# kolrs868_rx.net
KiCad netlist of a schematic drawn in EAGLE
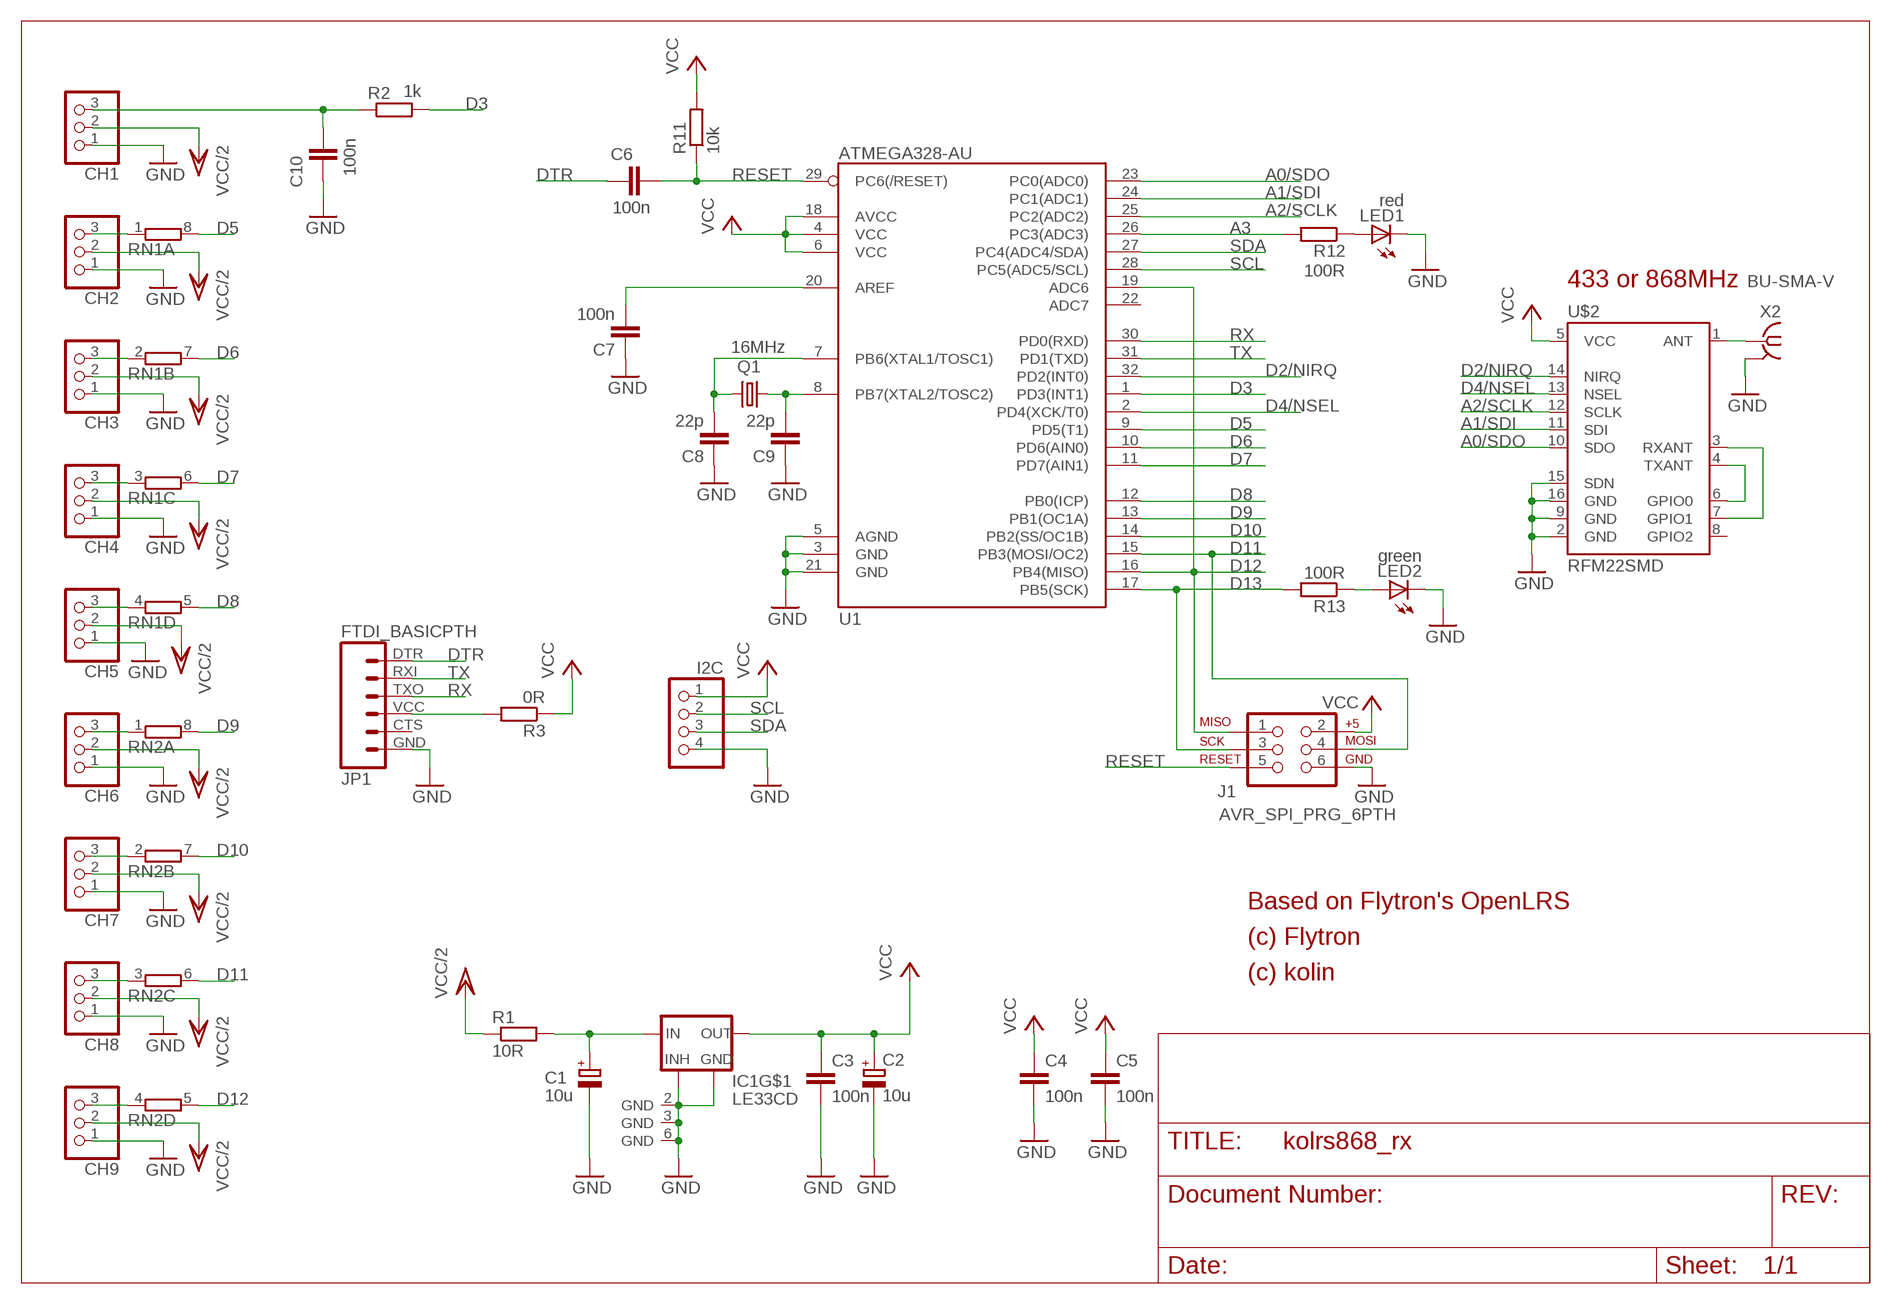
[diagram p0: schematic, sheet 1]

(export (version "E")
  (design (tool "Eeschema 10.0.6"))
  (components
    (comp (ref "C1")
      (value "10u")
      (footprint "eagle-import:SMC_B")
      (libsource (lib "eagle-import") (part "CPOL-EUSMCB"))
    )
    (comp (ref "C2")
      (value "10u")
      (footprint "eagle-import:SMC_B")
      (libsource (lib "eagle-import") (part "CPOL-EUSMCB"))
    )
    (comp (ref "C3")
      (value "100n")
      (footprint "eagle-import:M0805")
      (libsource (lib "eagle-import") (part "C-EU_KOLIN"))
    )
    (comp (ref "C4")
      (value "100n")
      (footprint "eagle-import:M0805")
      (libsource (lib "eagle-import") (part "C-EU_KOLIN"))
    )
    (comp (ref "C5")
      (value "100n")
      (footprint "eagle-import:M0805")
      (libsource (lib "eagle-import") (part "C-EU_KOLIN"))
    )
    (comp (ref "C6")
      (value "100n")
      (footprint "eagle-import:M0805")
      (libsource (lib "eagle-import") (part "C-EU_KOLIN"))
    )
    (comp (ref "C7")
      (value "100n")
      (footprint "eagle-import:M0805")
      (libsource (lib "eagle-import") (part "C-EU_KOLIN"))
    )
    (comp (ref "C8")
      (value "22p")
      (footprint "eagle-import:M0805")
      (libsource (lib "eagle-import") (part "C-EU_KOLIN"))
    )
    (comp (ref "C9")
      (value "22p")
      (footprint "eagle-import:M0805")
      (libsource (lib "eagle-import") (part "C-EU_KOLIN"))
    )
    (comp (ref "C10")
      (value "100n")
      (footprint "eagle-import:M0805")
      (libsource (lib "eagle-import") (part "C-EU_KOLIN"))
    )
    (comp (ref "CH1")
      (value "PINHD-1X3_KOLINOVO")
      (footprint "eagle-import:1X03")
      (libsource (lib "eagle-import") (part "PINHD-1X3_KOLINOVO"))
    )
    (comp (ref "CH2")
      (value "PINHD-1X3_KOLINOVO")
      (footprint "eagle-import:1X03")
      (libsource (lib "eagle-import") (part "PINHD-1X3_KOLINOVO"))
    )
    (comp (ref "CH3")
      (value "PINHD-1X3_KOLINOVO")
      (footprint "eagle-import:1X03")
      (libsource (lib "eagle-import") (part "PINHD-1X3_KOLINOVO"))
    )
    (comp (ref "CH4")
      (value "PINHD-1X3_KOLINOVO")
      (footprint "eagle-import:1X03")
      (libsource (lib "eagle-import") (part "PINHD-1X3_KOLINOVO"))
    )
    (comp (ref "CH5")
      (value "PINHD-1X3_KOLINOVO")
      (footprint "eagle-import:1X03")
      (libsource (lib "eagle-import") (part "PINHD-1X3_KOLINOVO"))
    )
    (comp (ref "CH6")
      (value "PINHD-1X3_KOLINOVO")
      (footprint "eagle-import:1X03")
      (libsource (lib "eagle-import") (part "PINHD-1X3_KOLINOVO"))
    )
    (comp (ref "CH7")
      (value "PINHD-1X3_KOLINOVO")
      (footprint "eagle-import:1X03")
      (libsource (lib "eagle-import") (part "PINHD-1X3_KOLINOVO"))
    )
    (comp (ref "CH8")
      (value "PINHD-1X3_KOLINOVO")
      (footprint "eagle-import:1X03")
      (libsource (lib "eagle-import") (part "PINHD-1X3_KOLINOVO"))
    )
    (comp (ref "CH9")
      (value "PINHD-1X3_KOLINOVO")
      (footprint "eagle-import:1X03")
      (libsource (lib "eagle-import") (part "PINHD-1X3_KOLINOVO"))
    )
    (comp (ref "I2C")
      (value "PINHD-1X4")
      (footprint "eagle-import:1X04")
      (libsource (lib "eagle-import") (part "PINHD-1X4"))
    )
    (comp (ref "IC1")
      (value "LE33CD")
      (footprint "eagle-import:SO8")
      (libsource (lib "eagle-import") (part "LE33CD"))
    )
    (comp (ref "J1")
      (value "AVR_SPI_PRG_6PTH")
      (footprint "eagle-import:2X3")
      (libsource (lib "eagle-import") (part "AVR_SPI_PRG_6PTH"))
    )
    (comp (ref "JP1")
      (value "FTDI_BASICPTH")
      (footprint "eagle-import:FTDI_BASIC")
      (libsource (lib "eagle-import") (part "FTDI_BASICPTH"))
    )
    (comp (ref "LED1")
      (value "red")
      (footprint "eagle-import:CHIPLED_0805")
      (libsource (lib "eagle-import") (part "LEDCHIPLED_0805"))
    )
    (comp (ref "LED2")
      (value "green")
      (footprint "eagle-import:CHIPLED_0805")
      (libsource (lib "eagle-import") (part "LEDCHIPLED_0805"))
    )
    (comp (ref "Q1")
      (value "16MHz")
      (footprint "eagle-import:HC49UP")
      (libsource (lib "eagle-import") (part "CRYSTALHC49UP"))
    )
    (comp (ref "R1")
      (value "10R")
      (footprint "eagle-import:M0805")
      (libsource (lib "eagle-import") (part "R-EU_KOLINM0805"))
    )
    (comp (ref "R2")
      (value "1k")
      (footprint "eagle-import:M0805")
      (libsource (lib "eagle-import") (part "R-EU_KOLINM0805"))
    )
    (comp (ref "R3")
      (value "0R")
      (footprint "eagle-import:M0805")
      (libsource (lib "eagle-import") (part "R-EU_KOLINM0805"))
    )
    (comp (ref "R11")
      (value "10k")
      (footprint "eagle-import:M0805")
      (libsource (lib "eagle-import") (part "R-EU_KOLINM0805"))
    )
    (comp (ref "R12")
      (value "100R")
      (footprint "eagle-import:M0805")
      (libsource (lib "eagle-import") (part "R-EU_KOLINM0805"))
    )
    (comp (ref "R13")
      (value "100R")
      (footprint "eagle-import:M0805")
      (libsource (lib "eagle-import") (part "R-EU_KOLINM0805"))
    )
    (comp (ref "RN1")
      (value "4R-NCAY16")
      (footprint "eagle-import:CAY16")
      (libsource (lib "eagle-import") (part "4R-NCAY16"))
    )
    (comp (ref "RN2")
      (value "4R-NCAY16")
      (footprint "eagle-import:CAY16")
      (libsource (lib "eagle-import") (part "4R-NCAY16"))
    )
    (comp (ref "U$2")
      (value "RFM22SMD")
      (footprint "eagle-import:RFM22-XXX-S2")
      (libsource (lib "eagle-import") (part "RFM22SMD"))
    )
    (comp (ref "U1")
      (value "ATMEGA328-AU")
      (footprint "eagle-import:TQFP32-08")
      (libsource (lib "eagle-import") (part "ATMEGA168"))
    )
    (comp (ref "X2")
      (value "BU-SMA-V")
      (footprint "eagle-import:BU-SMA-V")
      (libsource (lib "eagle-import") (part "BU-SMA-V"))
    )
  )
  (nets
    (net (code "1") (name "/A0{slash}SDO") (class "Default")
      (node (ref "U$2") (pin "10") (pinfunction "SDO_10") (pintype "output"))
      (node (ref "U1") (pin "23") (pinfunction "PC0(ADC0)_23") (pintype "bidirectional"))
    )
    (net (code "2") (name "/A1{slash}SDI") (class "Default")
      (node (ref "U$2") (pin "11") (pinfunction "SDI_11") (pintype "input"))
      (node (ref "U1") (pin "24") (pinfunction "PC1(ADC1)_24") (pintype "bidirectional"))
    )
    (net (code "3") (name "/A2{slash}SCLK") (class "Default")
      (node (ref "U$2") (pin "12") (pinfunction "SCLK_12") (pintype "input"))
      (node (ref "U1") (pin "25") (pinfunction "PC2(ADC2)_25") (pintype "bidirectional"))
    )
    (net (code "4") (name "/A3") (class "Default")
      (node (ref "R12") (pin "2") (pinfunction "2_2") (pintype "passive"))
      (node (ref "U1") (pin "26") (pinfunction "PC3(ADC3)_26") (pintype "bidirectional"))
    )
    (net (code "5") (name "/D2{slash}NIRQ") (class "Default")
      (node (ref "U$2") (pin "14") (pinfunction "NIRQ_14") (pintype "output"))
      (node (ref "U1") (pin "32") (pinfunction "PD2(INT0)_32") (pintype "bidirectional"))
    )
    (net (code "6") (name "/D3") (class "Default")
      (node (ref "R2") (pin "2") (pinfunction "2_2") (pintype "passive"))
      (node (ref "U1") (pin "1") (pinfunction "PD3(INT1)_1") (pintype "bidirectional"))
    )
    (net (code "7") (name "/D4{slash}NSEL") (class "Default")
      (node (ref "U$2") (pin "13") (pinfunction "NSEL_13") (pintype "input"))
      (node (ref "U1") (pin "2") (pinfunction "PD4(XCK/T0)_2") (pintype "bidirectional"))
    )
    (net (code "8") (name "/D5") (class "Default")
      (node (ref "RN1") (pin "8") (pinfunction "2_8") (pintype "passive"))
      (node (ref "U1") (pin "9") (pinfunction "PD5(T1)_9") (pintype "bidirectional"))
    )
    (net (code "9") (name "/D6") (class "Default")
      (node (ref "RN1") (pin "7") (pinfunction "2_7") (pintype "passive"))
      (node (ref "U1") (pin "10") (pinfunction "PD6(AIN0)_10") (pintype "bidirectional"))
    )
    (net (code "10") (name "/D7") (class "Default")
      (node (ref "RN1") (pin "6") (pinfunction "2_6") (pintype "passive"))
      (node (ref "U1") (pin "11") (pinfunction "PD7(AIN1)_11") (pintype "bidirectional"))
    )
    (net (code "11") (name "/D8") (class "Default")
      (node (ref "RN1") (pin "5") (pinfunction "2_5") (pintype "passive"))
      (node (ref "U1") (pin "12") (pinfunction "PB0(ICP)_12") (pintype "bidirectional"))
    )
    (net (code "12") (name "/D9") (class "Default")
      (node (ref "RN2") (pin "8") (pinfunction "2_8") (pintype "passive"))
      (node (ref "U1") (pin "13") (pinfunction "PB1(OC1A)_13") (pintype "bidirectional"))
    )
    (net (code "13") (name "/D10") (class "Default")
      (node (ref "RN2") (pin "7") (pinfunction "2_7") (pintype "passive"))
      (node (ref "U1") (pin "14") (pinfunction "PB2(SS/OC1B)_14") (pintype "bidirectional"))
    )
    (net (code "14") (name "/D11") (class "Default")
      (node (ref "J1") (pin "4") (pinfunction "4_4") (pintype "passive"))
      (node (ref "RN2") (pin "6") (pinfunction "2_6") (pintype "passive"))
      (node (ref "U1") (pin "15") (pinfunction "PB3(MOSI/OC2)_15") (pintype "bidirectional"))
    )
    (net (code "15") (name "/D12") (class "Default")
      (node (ref "J1") (pin "1") (pinfunction "1_1") (pintype "passive"))
      (node (ref "RN2") (pin "5") (pinfunction "2_5") (pintype "passive"))
      (node (ref "U1") (pin "16") (pinfunction "PB4(MISO)_16") (pintype "bidirectional"))
      (node (ref "U1") (pin "19") (pinfunction "ADC6_19") (pintype "bidirectional"))
    )
    (net (code "16") (name "/D13") (class "Default")
      (node (ref "J1") (pin "3") (pinfunction "3_3") (pintype "passive"))
      (node (ref "R13") (pin "2") (pinfunction "2_2") (pintype "passive"))
      (node (ref "U1") (pin "17") (pinfunction "PB5(SCK)_17") (pintype "bidirectional"))
    )
    (net (code "17") (name "/DTR") (class "Default")
      (node (ref "C6") (pin "1") (pinfunction "1_1") (pintype "passive"))
      (node (ref "JP1") (pin "DTR") (pinfunction "1_DTR") (pintype "passive"))
    )
    (net (code "18") (name "/RESET") (class "Default")
      (node (ref "C6") (pin "2") (pinfunction "2_2") (pintype "passive"))
      (node (ref "J1") (pin "5") (pinfunction "5_5") (pintype "passive"))
      (node (ref "R11") (pin "1") (pinfunction "1_1") (pintype "passive"))
      (node (ref "U1") (pin "29") (pinfunction "PC6(/RESET)_29") (pintype "bidirectional"))
    )
    (net (code "19") (name "/RX") (class "Default")
      (node (ref "JP1") (pin "TXO") (pinfunction "3_TXO") (pintype "passive"))
      (node (ref "U1") (pin "30") (pinfunction "PD0(RXD)_30") (pintype "bidirectional"))
    )
    (net (code "20") (name "/SCL") (class "Default")
      (node (ref "I2C") (pin "2") (pinfunction "2_2") (pintype "passive"))
      (node (ref "U1") (pin "28") (pinfunction "PC5(ADC5/SCL)_28") (pintype "bidirectional"))
    )
    (net (code "21") (name "/SDA") (class "Default")
      (node (ref "I2C") (pin "3") (pinfunction "3_3") (pintype "passive"))
      (node (ref "U1") (pin "27") (pinfunction "PC4(ADC4/SDA)_27") (pintype "bidirectional"))
    )
    (net (code "22") (name "/TX") (class "Default")
      (node (ref "JP1") (pin "RXI") (pinfunction "2_RXI") (pintype "passive"))
      (node (ref "U1") (pin "31") (pinfunction "PD1(TXD)_31") (pintype "bidirectional"))
    )
    (net (code "23") (name "GND") (class "Default")
      (node (ref "C1") (pin "-") (pinfunction "-_-") (pintype "passive"))
      (node (ref "C10") (pin "1") (pinfunction "1_1") (pintype "passive"))
      (node (ref "C2") (pin "-") (pinfunction "-_-") (pintype "passive"))
      (node (ref "C3") (pin "2") (pinfunction "2_2") (pintype "passive"))
      (node (ref "C4") (pin "2") (pinfunction "2_2") (pintype "passive"))
      (node (ref "C5") (pin "2") (pinfunction "2_2") (pintype "passive"))
      (node (ref "C7") (pin "1") (pinfunction "1_1") (pintype "passive"))
      (node (ref "C8") (pin "1") (pinfunction "1_1") (pintype "passive"))
      (node (ref "C9") (pin "1") (pinfunction "1_1") (pintype "passive"))
      (node (ref "CH1") (pin "1") (pinfunction "1_1") (pintype "passive"))
      (node (ref "CH2") (pin "1") (pinfunction "1_1") (pintype "passive"))
      (node (ref "CH3") (pin "1") (pinfunction "1_1") (pintype "passive"))
      (node (ref "CH4") (pin "1") (pinfunction "1_1") (pintype "passive"))
      (node (ref "CH5") (pin "1") (pinfunction "1_1") (pintype "passive"))
      (node (ref "CH6") (pin "1") (pinfunction "1_1") (pintype "passive"))
      (node (ref "CH7") (pin "1") (pinfunction "1_1") (pintype "passive"))
      (node (ref "CH8") (pin "1") (pinfunction "1_1") (pintype "passive"))
      (node (ref "CH9") (pin "1") (pinfunction "1_1") (pintype "passive"))
      (node (ref "I2C") (pin "4") (pinfunction "4_4") (pintype "passive"))
      (node (ref "IC1") (pin "2") (pinfunction "GND_2") (pintype "power_in"))
      (node (ref "IC1") (pin "3") (pinfunction "GND_3") (pintype "power_in"))
      (node (ref "IC1") (pin "5") (pinfunction "INHIBIT_5") (pintype "input"))
      (node (ref "IC1") (pin "6") (pinfunction "GND_6") (pintype "power_in"))
      (node (ref "IC1") (pin "7") (pinfunction "GND_7") (pintype "input"))
      (node (ref "J1") (pin "6") (pinfunction "6_6") (pintype "passive"))
      (node (ref "JP1") (pin "GND") (pinfunction "6_GND") (pintype "passive"))
      (node (ref "LED1") (pin "C") (pinfunction "C_C") (pintype "passive"))
      (node (ref "LED2") (pin "C") (pinfunction "C_C") (pintype "passive"))
      (node (ref "U$2") (pin "15") (pinfunction "SDN_15") (pintype "input"))
      (node (ref "U$2") (pin "16") (pinfunction "GND_16") (pintype "power_in"))
      (node (ref "U$2") (pin "2") (pinfunction "GND_2") (pintype "power_in"))
      (node (ref "U$2") (pin "9") (pinfunction "GND_9") (pintype "power_in"))
      (node (ref "U1") (pin "21") (pinfunction "GND_21") (pintype "bidirectional"))
      (node (ref "U1") (pin "3") (pinfunction "GND_3") (pintype "bidirectional"))
      (node (ref "U1") (pin "5") (pinfunction "AGND_5") (pintype "bidirectional"))
      (node (ref "X2") (pin "2") (pinfunction "GND_2") (pintype "power_in"))
    )
    (net (code "24") (name "Net-(C10-Pad2)") (class "Default")
      (node (ref "C10") (pin "2") (pinfunction "2_2") (pintype "passive"))
      (node (ref "CH1") (pin "3") (pinfunction "3_3") (pintype "passive"))
      (node (ref "R2") (pin "1") (pinfunction "1_1") (pintype "passive"))
    )
    (net (code "25") (name "Net-(CH2-Pad3)") (class "Default")
      (node (ref "CH2") (pin "3") (pinfunction "3_3") (pintype "passive"))
      (node (ref "RN1") (pin "1") (pinfunction "1_1") (pintype "passive"))
    )
    (net (code "26") (name "Net-(CH6-Pad3)") (class "Default")
      (node (ref "CH6") (pin "3") (pinfunction "3_3") (pintype "passive"))
      (node (ref "RN2") (pin "1") (pinfunction "1_1") (pintype "passive"))
    )
    (net (code "27") (name "Net-(IC1A-IN)") (class "Default")
      (node (ref "C1") (pin "+") (pinfunction "+_+") (pintype "passive"))
      (node (ref "IC1") (pin "8") (pinfunction "IN_8") (pintype "input"))
      (node (ref "R1") (pin "2") (pinfunction "2_2") (pintype "passive"))
    )
    (net (code "28") (name "Net-(JP1-4)") (class "Default")
      (node (ref "JP1") (pin "VCC") (pinfunction "4_VCC") (pintype "passive"))
      (node (ref "R3") (pin "2") (pinfunction "2_2") (pintype "passive"))
    )
    (net (code "29") (name "Net-(LED1-PadA)") (class "Default")
      (node (ref "LED1") (pin "A") (pinfunction "A_A") (pintype "passive"))
      (node (ref "R12") (pin "1") (pinfunction "1_1") (pintype "passive"))
    )
    (net (code "30") (name "Net-(LED2-PadA)") (class "Default")
      (node (ref "LED2") (pin "A") (pinfunction "A_A") (pintype "passive"))
      (node (ref "R13") (pin "1") (pinfunction "1_1") (pintype "passive"))
    )
    (net (code "31") (name "Net-(RN1B-1)") (class "Default")
      (node (ref "CH3") (pin "3") (pinfunction "3_3") (pintype "passive"))
      (node (ref "RN1") (pin "2") (pinfunction "1_2") (pintype "passive"))
    )
    (net (code "32") (name "Net-(RN1C-1)") (class "Default")
      (node (ref "CH4") (pin "3") (pinfunction "3_3") (pintype "passive"))
      (node (ref "RN1") (pin "3") (pinfunction "1_3") (pintype "passive"))
    )
    (net (code "33") (name "Net-(RN1D-1)") (class "Default")
      (node (ref "CH5") (pin "3") (pinfunction "3_3") (pintype "passive"))
      (node (ref "RN1") (pin "4") (pinfunction "1_4") (pintype "passive"))
    )
    (net (code "34") (name "Net-(RN2B-1)") (class "Default")
      (node (ref "CH7") (pin "3") (pinfunction "3_3") (pintype "passive"))
      (node (ref "RN2") (pin "2") (pinfunction "1_2") (pintype "passive"))
    )
    (net (code "35") (name "Net-(RN2C-1)") (class "Default")
      (node (ref "CH8") (pin "3") (pinfunction "3_3") (pintype "passive"))
      (node (ref "RN2") (pin "3") (pinfunction "1_3") (pintype "passive"))
    )
    (net (code "36") (name "Net-(RN2D-1)") (class "Default")
      (node (ref "CH9") (pin "3") (pinfunction "3_3") (pintype "passive"))
      (node (ref "RN2") (pin "4") (pinfunction "1_4") (pintype "passive"))
    )
    (net (code "37") (name "Net-(U$2-ANT)") (class "Default")
      (node (ref "U$2") (pin "1") (pinfunction "ANT_1") (pintype "bidirectional"))
      (node (ref "X2") (pin "1") (pinfunction "1_1") (pintype "passive"))
    )
    (net (code "38") (name "Net-(U$2-GPIO0)") (class "Default")
      (node (ref "U$2") (pin "4") (pinfunction "TXANT_4") (pintype "input"))
      (node (ref "U$2") (pin "6") (pinfunction "GPIO0_6") (pintype "bidirectional"))
    )
    (net (code "39") (name "Net-(U$2-GPIO1)") (class "Default")
      (node (ref "U$2") (pin "3") (pinfunction "RXANT_3") (pintype "input"))
      (node (ref "U$2") (pin "7") (pinfunction "GPIO1_7") (pintype "bidirectional"))
    )
    (net (code "40") (name "Net-(U1-AREF)") (class "Default")
      (node (ref "C7") (pin "2") (pinfunction "2_2") (pintype "passive"))
      (node (ref "U1") (pin "20") (pinfunction "AREF_20") (pintype "bidirectional"))
    )
    (net (code "41") (name "Net-(U1-PB6(XTAL1{slash}TOSC1))") (class "Default")
      (node (ref "C8") (pin "2") (pinfunction "2_2") (pintype "passive"))
      (node (ref "Q1") (pin "2") (pinfunction "2_2") (pintype "passive"))
      (node (ref "U1") (pin "7") (pinfunction "PB6(XTAL1/TOSC1)_7") (pintype "bidirectional"))
    )
    (net (code "42") (name "Net-(U1-PB7(XTAL2{slash}TOSC2))") (class "Default")
      (node (ref "C9") (pin "2") (pinfunction "2_2") (pintype "passive"))
      (node (ref "Q1") (pin "1") (pinfunction "1_1") (pintype "passive"))
      (node (ref "U1") (pin "8") (pinfunction "PB7(XTAL2/TOSC2)_8") (pintype "bidirectional"))
    )
    (net (code "43") (name "VCC") (class "Default")
      (node (ref "C2") (pin "+") (pinfunction "+_+") (pintype "passive"))
      (node (ref "C3") (pin "1") (pinfunction "1_1") (pintype "passive"))
      (node (ref "C4") (pin "1") (pinfunction "1_1") (pintype "passive"))
      (node (ref "C5") (pin "1") (pinfunction "1_1") (pintype "passive"))
      (node (ref "I2C") (pin "1") (pinfunction "1_1") (pintype "passive"))
      (node (ref "IC1") (pin "1") (pinfunction "OUT_1") (pintype "passive"))
      (node (ref "J1") (pin "2") (pinfunction "2_2") (pintype "passive"))
      (node (ref "R11") (pin "2") (pinfunction "2_2") (pintype "passive"))
      (node (ref "R3") (pin "1") (pinfunction "1_1") (pintype "passive"))
      (node (ref "U$2") (pin "5") (pinfunction "VCC_5") (pintype "bidirectional"))
      (node (ref "U1") (pin "18") (pinfunction "AVCC_18") (pintype "bidirectional"))
      (node (ref "U1") (pin "4") (pinfunction "VCC_4") (pintype "bidirectional"))
      (node (ref "U1") (pin "6") (pinfunction "VCC_6") (pintype "bidirectional"))
    )
    (net (code "44") (name "VCC{slash}2") (class "Default")
      (node (ref "CH1") (pin "2") (pinfunction "2_2") (pintype "passive"))
      (node (ref "CH2") (pin "2") (pinfunction "2_2") (pintype "passive"))
      (node (ref "CH3") (pin "2") (pinfunction "2_2") (pintype "passive"))
      (node (ref "CH4") (pin "2") (pinfunction "2_2") (pintype "passive"))
      (node (ref "CH5") (pin "2") (pinfunction "2_2") (pintype "passive"))
      (node (ref "CH6") (pin "2") (pinfunction "2_2") (pintype "passive"))
      (node (ref "CH7") (pin "2") (pinfunction "2_2") (pintype "passive"))
      (node (ref "CH8") (pin "2") (pinfunction "2_2") (pintype "passive"))
      (node (ref "CH9") (pin "2") (pinfunction "2_2") (pintype "passive"))
      (node (ref "R1") (pin "1") (pinfunction "1_1") (pintype "passive"))
    )
    (net (code "45") (name "unconnected-(JP1-5-PadCTS)") (class "Default")
      (node (ref "JP1") (pin "CTS") (pinfunction "5_CTS") (pintype "passive"))
    )
    (net (code "46") (name "unconnected-(U$2-GPIO2-Pad8)") (class "Default")
      (node (ref "U$2") (pin "8") (pinfunction "GPIO2_8") (pintype "bidirectional"))
    )
    (net (code "47") (name "unconnected-(U1-ADC7-Pad22)") (class "Default")
      (node (ref "U1") (pin "22") (pinfunction "ADC7_22") (pintype "bidirectional"))
    )
  )
)
